# 03_TOPOLOGY.net
KiCad netlist of a schematic drawn in Altium Designer
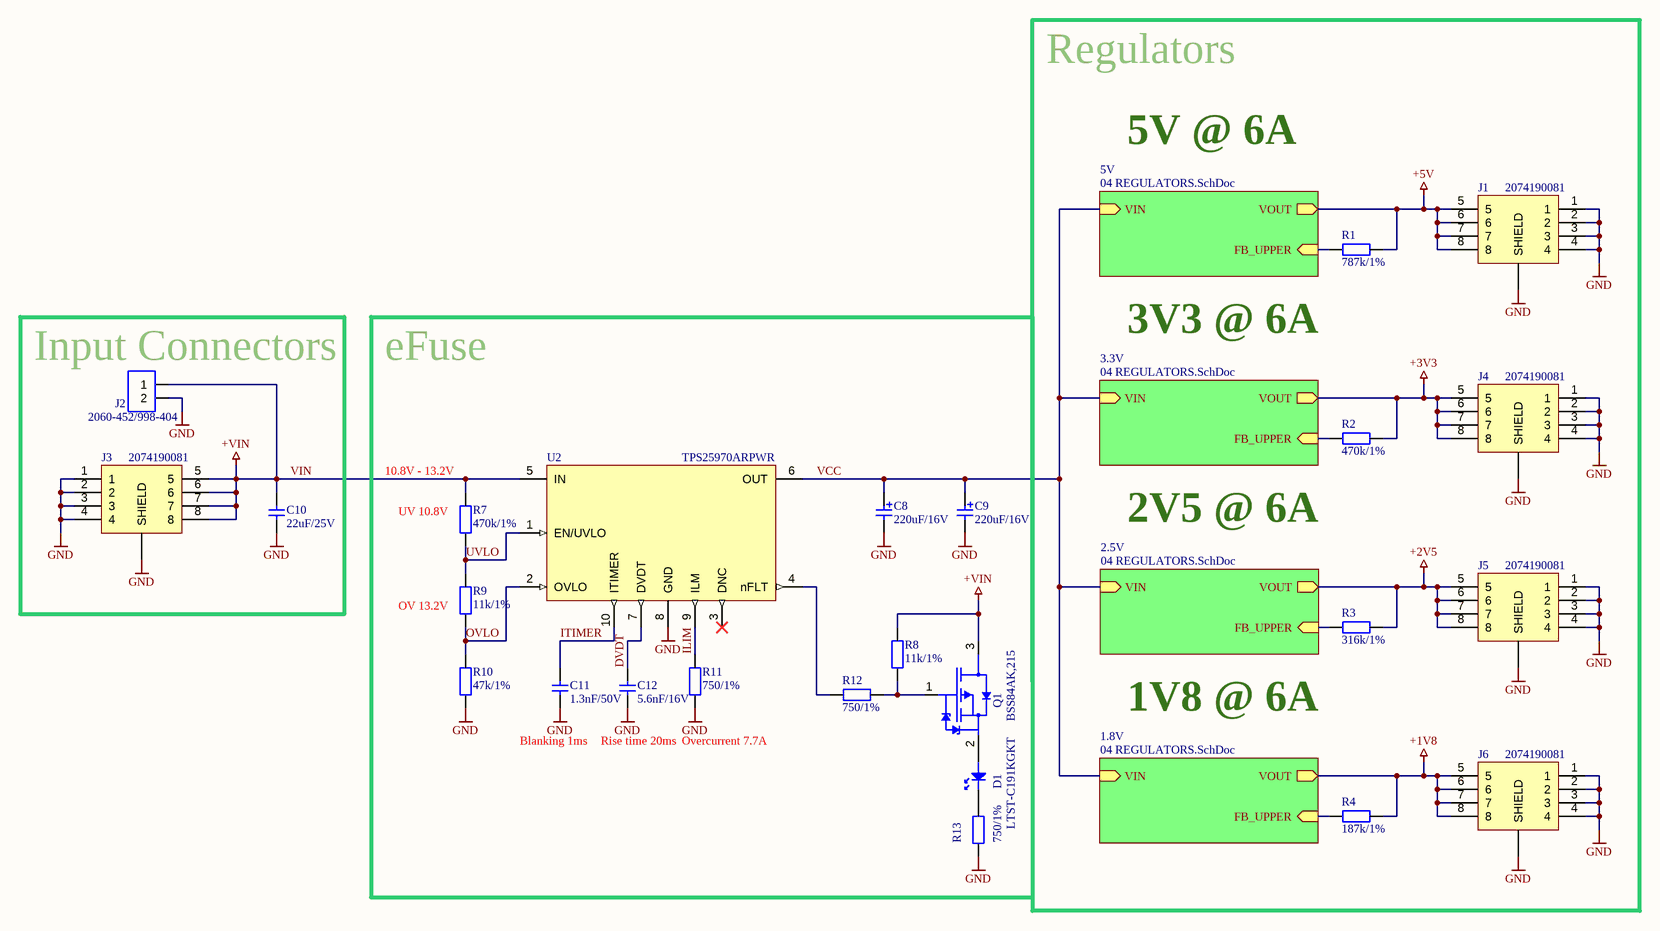
[diagram p0: 03 TOPOLOGY.SchDoc]

(export (version "E")
  (design (tool "Eeschema 10.0.6"))
  (components
    (comp (ref "C8")
      (value "220uF/16V")
      (footprint "TANTAL/2917")
      (description "220 µF Molded Tantalum Capacitors 16 V 2917 (7343 Metric) 500mOhm")
      (fields (field (name "MPN") "T491D227K016AT"))
      (libsource (lib "PowerModule") (part "T491D227K016AT"))
    )
    (comp (ref "C9")
      (value "220uF/16V")
      (footprint "TANTAL/2917")
      (description "220 µF Molded Tantalum Capacitors 16 V 2917 (7343 Metric) 500mOhm")
      (fields (field (name "MPN") "T491D227K016AT"))
      (libsource (lib "PowerModule") (part "T491D227K016AT"))
    )
    (comp (ref "C10")
      (value "22uF/25V")
      (footprint "CAPC2012X14M")
      (description "22 µF ±20% 25V Ceramic Capacitor X5R 0805 (2012 Metric)")
      (fields (field (name "MPN") "GRT21BR61E226ME13L"))
      (libsource (lib "PowerModule") (part "GRT21BR61E226ME13L"))
    )
    (comp (ref "C11")
      (value "1.3nF/50V")
      (footprint "CAPC1005X07M")
      (description "1300 pF ±5% 50V Ceramic Capacitor C0G, NP0 0402 (1005 Metric)")
      (fields (field (name "MPN") "C0402C132J5GAC7867"))
      (libsource (lib "PowerModule") (part "C0402C132J5GAC7867"))
    )
    (comp (ref "C12")
      (value "5.6nF/16V")
      (footprint "CAPC1005X07M")
      (description "5600 pF ±10% 16V Ceramic Capacitor X7R 0402 (1005 Metric)")
      (fields (field (name "MPN") "CC0402KRX7R7BB562"))
      (libsource (lib "PowerModule") (part "CC0402KRX7R7BB562"))
    )
    (comp (ref "D1")
      (value "LTST-C191KGKT")
      (footprint "LED-0603")
      (description "Green 571nm LED Indication - Discrete 2V 0603 (1608 Metric)")
      (libsource (lib "PowerModule") (part "LTST-C191KGKT"))
    )
    (comp (ref "J1")
      (value "2074190081")
      (footprint "2074190081")
      (description "8 (4 + 4 Power) Position Connector Receptacle, Center Strip Contacts Surface Mount Gold")
      (libsource (lib "") (part "2074190081_1"))
    )
    (comp (ref "J2")
      (value "2060-452/998-404")
      (footprint "2060-452/998-404")
      (description "2 Position Wire to Board Terminal Block Horizontal with Board 0.157\" (4.00mm) Surface Mount")
      (libsource (lib "PowerModule") (part "2060-452/998-404"))
    )
    (comp (ref "J3")
      (value "2074190081")
      (footprint "2074190081")
      (description "8 (4 + 4 Power) Position Connector Receptacle, Center Strip Contacts Surface Mount Gold")
      (libsource (lib "PowerModule") (part "2074190081"))
    )
    (comp (ref "J4")
      (value "2074190081")
      (footprint "2074190081")
      (description "8 (4 + 4 Power) Position Connector Receptacle, Center Strip Contacts Surface Mount Gold")
      (libsource (lib "") (part "2074190081_1"))
    )
    (comp (ref "J5")
      (value "2074190081")
      (footprint "2074190081")
      (description "8 (4 + 4 Power) Position Connector Receptacle, Center Strip Contacts Surface Mount Gold")
      (libsource (lib "") (part "2074190081_1"))
    )
    (comp (ref "J6")
      (value "2074190081")
      (footprint "2074190081")
      (description "8 (4 + 4 Power) Position Connector Receptacle, Center Strip Contacts Surface Mount Gold")
      (libsource (lib "") (part "2074190081_1"))
    )
    (comp (ref "Q1")
      (value "BSS84AK,215")
      (footprint "SOT95P230X110-3M")
      (description "P-Channel 50 V 180mA (Ta) 350mW (Ta), 1.14W (Tc) Surface Mount TO-236AB")
      (libsource (lib "PowerModule") (part "BSS84AK,215"))
    )
    (comp (ref "R1")
      (value "787k/1%")
      (footprint "RESC1005X04M")
      (description "787 kOhms ±1% 0.063W, 1/16W Chip Resistor 0402 (1005 Metric) Automotive AEC-Q200 Thick Film")
      (fields (field (name "MPN") "CRCW0402787KFKED"))
      (libsource (lib "PowerModule") (part "CRCW0402787KFKED"))
    )
    (comp (ref "R2")
      (value "470k/1%")
      (footprint "RESC1005X04M")
      (description "470 kOhms ±1% 0.063W, 1/16W Chip Resistor 0402 (1005 Metric) Automotive AEC-Q200 Thick Film")
      (fields (field (name "MPN") "RMCF0402FT470K"))
      (libsource (lib "PowerModule") (part "CRCW0402787KFKED_1RMCF0402FT470K"))
    )
    (comp (ref "R3")
      (value "316k/1%")
      (footprint "RESC1005X04M")
      (description "316 kOhms ±1% 0.063W, 1/16W Chip Resistor 0402 (1005 Metric) Automotive AEC-Q200 Thick Film")
      (fields (field (name "MPN") "CRCW0402316KFKED"))
      (libsource (lib "PowerModule") (part "CRCW0402316KFKED"))
    )
    (comp (ref "R4")
      (value "187k/1%")
      (footprint "RESC1005X04M")
      (description "187 kOhms ±1% 0.063W, 1/16W Chip Resistor 0402 (1005 Metric) Automotive AEC-Q200 Thick Film")
      (fields (field (name "MPN") "CRCW0402187KFKED"))
      (libsource (lib "PowerModule") (part "CRCW0402187KFKED"))
    )
    (comp (ref "R7")
      (value "470k/1%")
      (footprint "RESC1005X04M")
      (description "470 kOhms ±1% 0.063W, 1/16W Chip Resistor 0402 (1005 Metric) Automotive AEC-Q200 Thick Film")
      (fields (field (name "MPN") "RMCF0402FT470K"))
      (libsource (lib "PowerModule") (part "CRCW0402787KFKED_1RMCF0402FT470K"))
    )
    (comp (ref "R8")
      (value "11k/1%")
      (footprint "RESC1005X04M")
      (description "11 kOhms ±1% 0.063W, 1/16W Chip Resistor 0402 (1005 Metric) Moisture Resistant Thick Film")
      (fields (field (name "MPN") "RC0402FR-0711KL"))
      (libsource (lib "PowerModule") (part "RC0402FR-0711KL"))
    )
    (comp (ref "R9")
      (value "11k/1%")
      (footprint "RESC1005X04M")
      (description "11 kOhms ±1% 0.063W, 1/16W Chip Resistor 0402 (1005 Metric) Moisture Resistant Thick Film")
      (fields (field (name "MPN") "RC0402FR-0711KL"))
      (libsource (lib "PowerModule") (part "RC0402FR-0711KL"))
    )
    (comp (ref "R10")
      (value "47k/1%")
      (footprint "RESC1005X04M")
      (description "47 kOhms ±1% 0.1W, 1/10W Chip Resistor 0402 (1005 Metric) Automotive AEC-Q200 Thick Film")
      (fields (field (name "MPN") "ERJ-2RKF4702X"))
      (libsource (lib "PowerModule") (part "ERJ-2RKF4702X"))
    )
    (comp (ref "R11")
      (value "750/1%")
      (footprint "RESC1005X04M")
      (description "750 Ohms ±1% 0.063W, 1/16W Chip Resistor 0402 (1005 Metric) Moisture Resistant Thick Film")
      (fields (field (name "MPN") "RC0402FR-07750RL"))
      (libsource (lib "PowerModule") (part "RC0402FR-07750RL"))
    )
    (comp (ref "R12")
      (value "750/1%")
      (footprint "RESC1005X04M")
      (description "750 Ohms ±1% 0.063W, 1/16W Chip Resistor 0402 (1005 Metric) Moisture Resistant Thick Film")
      (fields (field (name "MPN") "RC0402FR-07750RL"))
      (libsource (lib "PowerModule") (part "RC0402FR-07750RL"))
    )
    (comp (ref "R13")
      (value "750/1%")
      (footprint "RESC1005X04M")
      (description "750 Ohms ±1% 0.063W, 1/16W Chip Resistor 0402 (1005 Metric) Moisture Resistant Thick Film")
      (fields (field (name "MPN") "RC0402FR-07750RL"))
      (libsource (lib "PowerModule") (part "RC0402FR-07750RL"))
    )
    (comp (ref "U2")
      (value "TPS25970ARPWR")
      (footprint "QFN45P200X200X100-16L")
      (description "2.7-V TO 23-V, 10-MOHM, 7-A EFUS")
      (libsource (lib "PowerModule") (part "TPS25970ARPWR"))
    )
  )
  (nets
    (net (code "1") (name "+1V8") (class "Default")
      (node (ref "J6") (pin "5") (pinfunction "5_5") (pintype "passive"))
      (node (ref "J6") (pin "6") (pinfunction "6_6") (pintype "passive"))
      (node (ref "J6") (pin "7") (pinfunction "7_7") (pintype "passive"))
      (node (ref "J6") (pin "8") (pinfunction "8_8") (pintype "passive"))
      (node (ref "R4") (pin "2") (pinfunction "2_2") (pintype "passive"))
    )
    (net (code "2") (name "+2V5") (class "Default")
      (node (ref "J5") (pin "5") (pinfunction "5_5") (pintype "passive"))
      (node (ref "J5") (pin "6") (pinfunction "6_6") (pintype "passive"))
      (node (ref "J5") (pin "7") (pinfunction "7_7") (pintype "passive"))
      (node (ref "J5") (pin "8") (pinfunction "8_8") (pintype "passive"))
      (node (ref "R3") (pin "2") (pinfunction "2_2") (pintype "passive"))
    )
    (net (code "3") (name "+3V3") (class "Default")
      (node (ref "J4") (pin "5") (pinfunction "5_5") (pintype "passive"))
      (node (ref "J4") (pin "6") (pinfunction "6_6") (pintype "passive"))
      (node (ref "J4") (pin "7") (pinfunction "7_7") (pintype "passive"))
      (node (ref "J4") (pin "8") (pinfunction "8_8") (pintype "passive"))
      (node (ref "R2") (pin "2") (pinfunction "2_2") (pintype "passive"))
    )
    (net (code "4") (name "+5V") (class "Default")
      (node (ref "J1") (pin "5") (pinfunction "5_5") (pintype "passive"))
      (node (ref "J1") (pin "6") (pinfunction "6_6") (pintype "passive"))
      (node (ref "J1") (pin "7") (pinfunction "7_7") (pintype "passive"))
      (node (ref "J1") (pin "8") (pinfunction "8_8") (pintype "passive"))
      (node (ref "R1") (pin "2") (pinfunction "2_2") (pintype "passive"))
    )
    (net (code "5") (name "+VIN") (class "Default")
      (node (ref "C10") (pin "2") (pinfunction "2_2") (pintype "passive"))
      (node (ref "J2") (pin "1") (pinfunction "1_1") (pintype "passive"))
      (node (ref "J3") (pin "5") (pinfunction "5_5") (pintype "passive"))
      (node (ref "J3") (pin "6") (pinfunction "6_6") (pintype "passive"))
      (node (ref "J3") (pin "7") (pinfunction "7_7") (pintype "passive"))
      (node (ref "J3") (pin "8") (pinfunction "8_8") (pintype "passive"))
      (node (ref "Q1") (pin "3") (pinfunction "D_3") (pintype "passive"))
      (node (ref "R7") (pin "2") (pinfunction "2_2") (pintype "passive"))
      (node (ref "R8") (pin "2") (pinfunction "2_2") (pintype "passive"))
      (node (ref "U2") (pin "5") (pinfunction "IN_5") (pintype "power_in"))
    )
    (net (code "6") (name "/DVDT") (class "Default")
      (node (ref "C12") (pin "2") (pinfunction "2_2") (pintype "passive"))
      (node (ref "U2") (pin "7") (pinfunction "DVDT_7") (pintype "output"))
    )
    (net (code "7") (name "/FB_UPPER") (class "Default")
      (node (ref "R1") (pin "1") (pinfunction "1_1") (pintype "passive"))
    )
    (net (code "8") (name "/FB_UPPER_1") (class "Default")
      (node (ref "R3") (pin "1") (pinfunction "1_1") (pintype "passive"))
    )
    (net (code "9") (name "/FB_UPPER_2") (class "Default")
      (node (ref "R2") (pin "1") (pinfunction "1_1") (pintype "passive"))
    )
    (net (code "10") (name "/FB_UPPER_3") (class "Default")
      (node (ref "R4") (pin "1") (pinfunction "1_1") (pintype "passive"))
    )
    (net (code "11") (name "/ILIM") (class "Default")
      (node (ref "R11") (pin "2") (pinfunction "2_2") (pintype "passive"))
      (node (ref "U2") (pin "9") (pinfunction "ILM_9") (pintype "output"))
    )
    (net (code "12") (name "/ITIMER") (class "Default")
      (node (ref "C11") (pin "2") (pinfunction "2_2") (pintype "passive"))
      (node (ref "U2") (pin "10") (pinfunction "ITIMER_10") (pintype "output"))
    )
    (net (code "13") (name "/OVLO") (class "Default")
      (node (ref "R10") (pin "2") (pinfunction "2_2") (pintype "passive"))
      (node (ref "R9") (pin "1") (pinfunction "1_1") (pintype "passive"))
      (node (ref "U2") (pin "2") (pinfunction "OVLO_2") (pintype "input"))
    )
    (net (code "14") (name "/UVLO") (class "Default")
      (node (ref "R7") (pin "1") (pinfunction "1_1") (pintype "passive"))
      (node (ref "R9") (pin "2") (pinfunction "2_2") (pintype "passive"))
      (node (ref "U2") (pin "1") (pinfunction "EN/UVLO_1") (pintype "input"))
    )
    (net (code "15") (name "/VCC") (class "Default")
      (node (ref "C8") (pin "1") (pinfunction "1_1") (pintype "passive"))
      (node (ref "C9") (pin "1") (pinfunction "1_1") (pintype "passive"))
      (node (ref "U2") (pin "6") (pinfunction "OUT_6") (pintype "power_in"))
    )
    (net (code "16") (name "GND") (class "Default")
      (node (ref "C10") (pin "1") (pinfunction "1_1") (pintype "passive"))
      (node (ref "C11") (pin "1") (pinfunction "1_1") (pintype "passive"))
      (node (ref "C12") (pin "1") (pinfunction "1_1") (pintype "passive"))
      (node (ref "C8") (pin "2") (pinfunction "2_2") (pintype "passive"))
      (node (ref "C9") (pin "2") (pinfunction "2_2") (pintype "passive"))
      (node (ref "J1") (pin "1") (pinfunction "1_1") (pintype "passive"))
      (node (ref "J1") (pin "2") (pinfunction "2_2") (pintype "passive"))
      (node (ref "J1") (pin "3") (pinfunction "3_3") (pintype "passive"))
      (node (ref "J1") (pin "4") (pinfunction "4_4") (pintype "passive"))
      (node (ref "J1") (pin "SHLD") (pinfunction "SHIELD_SHLD") (pintype "passive"))
      (node (ref "J2") (pin "2") (pinfunction "2_2") (pintype "passive"))
      (node (ref "J3") (pin "1") (pinfunction "1_1") (pintype "passive"))
      (node (ref "J3") (pin "2") (pinfunction "2_2") (pintype "passive"))
      (node (ref "J3") (pin "3") (pinfunction "3_3") (pintype "passive"))
      (node (ref "J3") (pin "4") (pinfunction "4_4") (pintype "passive"))
      (node (ref "J3") (pin "SHLD") (pinfunction "SHIELD_SHLD") (pintype "passive"))
      (node (ref "J4") (pin "1") (pinfunction "1_1") (pintype "passive"))
      (node (ref "J4") (pin "2") (pinfunction "2_2") (pintype "passive"))
      (node (ref "J4") (pin "3") (pinfunction "3_3") (pintype "passive"))
      (node (ref "J4") (pin "4") (pinfunction "4_4") (pintype "passive"))
      (node (ref "J4") (pin "SHLD") (pinfunction "SHIELD_SHLD") (pintype "passive"))
      (node (ref "J5") (pin "1") (pinfunction "1_1") (pintype "passive"))
      (node (ref "J5") (pin "2") (pinfunction "2_2") (pintype "passive"))
      (node (ref "J5") (pin "3") (pinfunction "3_3") (pintype "passive"))
      (node (ref "J5") (pin "4") (pinfunction "4_4") (pintype "passive"))
      (node (ref "J5") (pin "SHLD") (pinfunction "SHIELD_SHLD") (pintype "passive"))
      (node (ref "J6") (pin "1") (pinfunction "1_1") (pintype "passive"))
      (node (ref "J6") (pin "2") (pinfunction "2_2") (pintype "passive"))
      (node (ref "J6") (pin "3") (pinfunction "3_3") (pintype "passive"))
      (node (ref "J6") (pin "4") (pinfunction "4_4") (pintype "passive"))
      (node (ref "J6") (pin "SHLD") (pinfunction "SHIELD_SHLD") (pintype "passive"))
      (node (ref "R10") (pin "1") (pinfunction "1_1") (pintype "passive"))
      (node (ref "R11") (pin "1") (pinfunction "1_1") (pintype "passive"))
      (node (ref "R13") (pin "1") (pinfunction "1_1") (pintype "passive"))
      (node (ref "U2") (pin "8") (pinfunction "GND_8") (pintype "power_in"))
    )
    (net (code "17") (name "Net-(D1-Pad1)") (class "Default")
      (node (ref "D1") (pin "1") (pinfunction "1_1") (pintype "passive"))
      (node (ref "R13") (pin "2") (pinfunction "2_2") (pintype "passive"))
    )
    (net (code "18") (name "Net-(Q1-G)") (class "Default")
      (node (ref "Q1") (pin "1") (pinfunction "G_1") (pintype "passive"))
      (node (ref "R12") (pin "2") (pinfunction "2_2") (pintype "passive"))
      (node (ref "R8") (pin "1") (pinfunction "1_1") (pintype "passive"))
    )
    (net (code "19") (name "Net-(Q1-S)") (class "Default")
      (node (ref "D1") (pin "2") (pinfunction "2_2") (pintype "passive"))
      (node (ref "Q1") (pin "2") (pinfunction "S_2") (pintype "passive"))
    )
    (net (code "20") (name "Net-(U2-nFLT)") (class "Default")
      (node (ref "R12") (pin "1") (pinfunction "1_1") (pintype "passive"))
      (node (ref "U2") (pin "4") (pinfunction "nFLT_4") (pintype "output"))
    )
    (net (code "21") (name "unconnected-(U2-DNC-Pad3)") (class "Default")
      (node (ref "U2") (pin "3") (pinfunction "DNC_3") (pintype "output+no_connect"))
    )
  )
)
